# Jlink_V9.net
KiCad netlist of a schematic drawn in Altium Designer
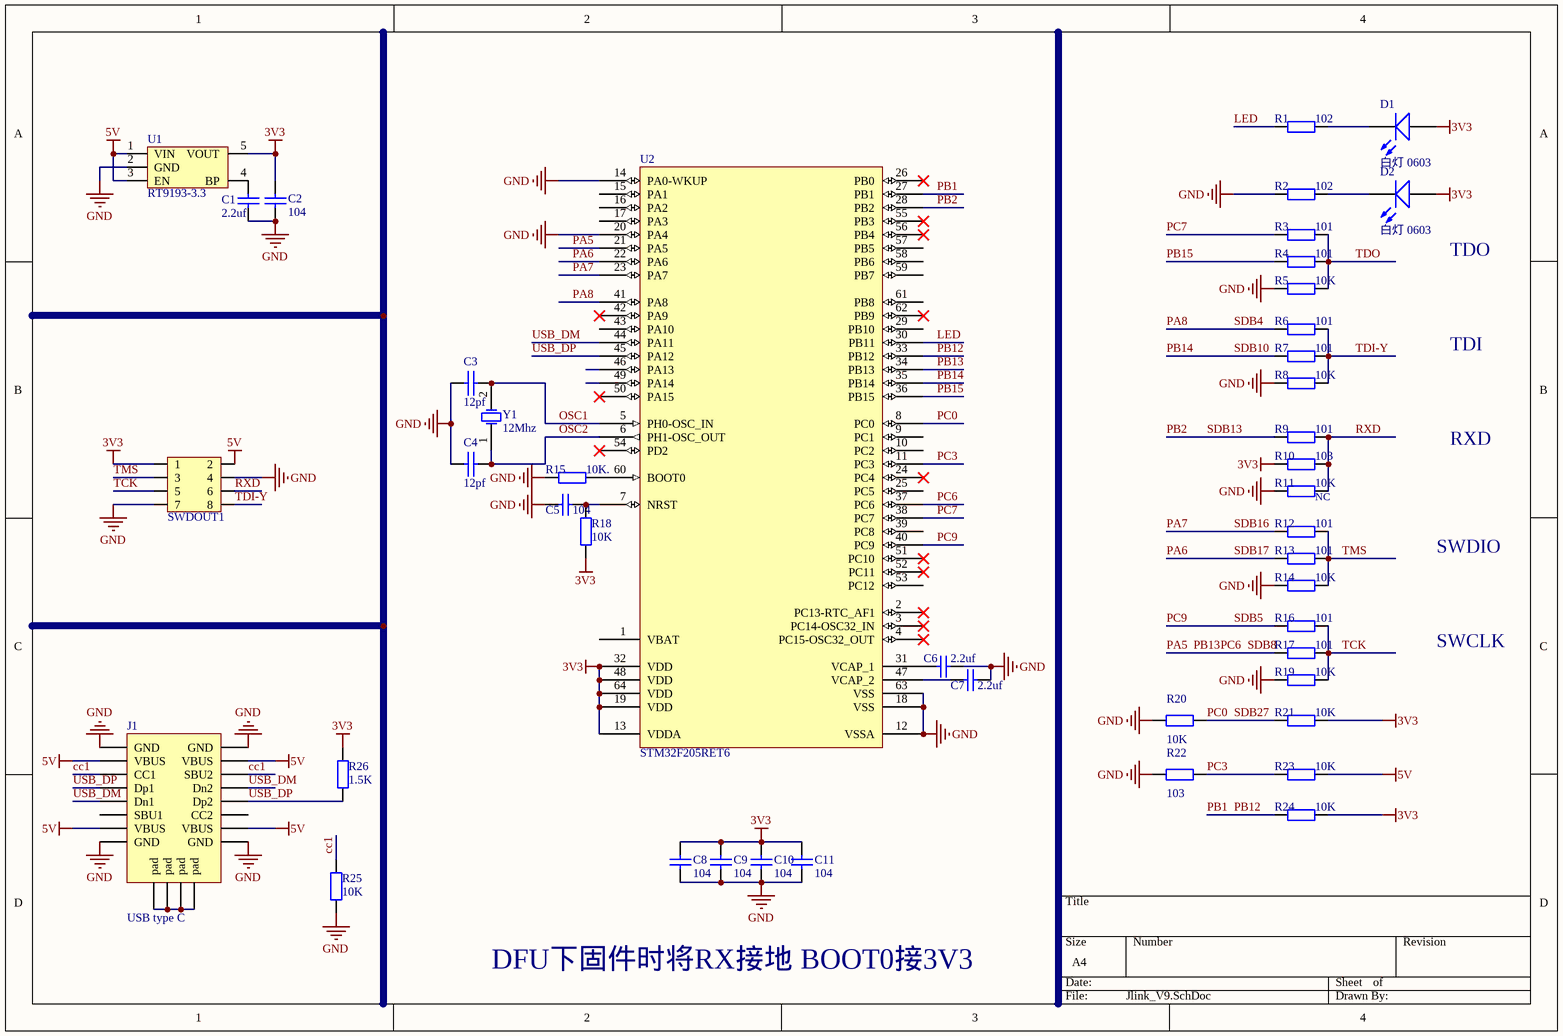
[diagram p0: Jlink_V9.SchDoc]

(export (version "E")
  (design (tool "Eeschema 10.0.6"))
  (components
    (comp (ref "C1")
      (value "2.2uf")
      (footprint "LC-0603_C")
      (description "Polarized Capacitor (Radial)")
      (fields (field (name "Comment") "Cap") (field (name "PUBLISHER") "Altium Limited"))
      (libsource (lib "Fantasy") (part "Cap"))
    )
    (comp (ref "C2")
      (value "104")
      (footprint "LC-0603_C")
      (description "Polarized Capacitor (Radial)")
      (fields (field (name "Comment") "Cap") (field (name "PUBLISHER") "Altium Limited"))
      (libsource (lib "Fantasy") (part "Cap"))
    )
    (comp (ref "C3") (value "12pf") (footprint "LC-0603_C") (libsource (lib "自创 (1)") (part "CAP")))
    (comp (ref "C4") (value "12pf") (footprint "LC-0603_C") (libsource (lib "自创 (1)") (part "CAP")))
    (comp (ref "C5")
      (value "104")
      (footprint "LC-0603_C")
      (description "Polarized Capacitor (Radial)")
      (fields (field (name "Comment") "Cap") (field (name "PUBLISHER") "Altium Limited"))
      (libsource (lib "Fantasy") (part "Cap"))
    )
    (comp (ref "C6")
      (value "2.2uf")
      (footprint "LC-0603_C")
      (description "Polarized Capacitor (Radial)")
      (fields (field (name "Comment") "Cap") (field (name "PUBLISHER") "Altium Limited"))
      (libsource (lib "Fantasy") (part "Cap"))
    )
    (comp (ref "C7")
      (value "2.2uf")
      (footprint "LC-0603_C")
      (description "Polarized Capacitor (Radial)")
      (fields (field (name "Comment") "Cap") (field (name "PUBLISHER") "Altium Limited"))
      (libsource (lib "Fantasy") (part "Cap"))
    )
    (comp (ref "C8")
      (value "104")
      (footprint "LC-0603_C")
      (description "Polarized Capacitor (Radial)")
      (fields (field (name "Comment") "Cap") (field (name "PUBLISHER") "Altium Limited"))
      (libsource (lib "Fantasy") (part "Cap"))
    )
    (comp (ref "C9")
      (value "104")
      (footprint "LC-0603_C")
      (description "Polarized Capacitor (Radial)")
      (fields (field (name "Comment") "Cap") (field (name "PUBLISHER") "Altium Limited"))
      (libsource (lib "Fantasy") (part "Cap"))
    )
    (comp (ref "C10")
      (value "104")
      (footprint "LC-0603_C")
      (description "Polarized Capacitor (Radial)")
      (fields (field (name "Comment") "Cap") (field (name "PUBLISHER") "Altium Limited"))
      (libsource (lib "Fantasy") (part "Cap"))
    )
    (comp (ref "C11")
      (value "104")
      (footprint "LC-0603_C")
      (description "Polarized Capacitor (Radial)")
      (fields (field (name "Comment") "Cap") (field (name "PUBLISHER") "Altium Limited"))
      (libsource (lib "Fantasy") (part "Cap"))
    )
    (comp (ref "D1")
      (value "白灯 0603")
      (footprint "0603_LED_S1")
      (description "发光二极管")
      (libsource (lib "Miscellaneous Devices LC") (part "0603 白灯"))
    )
    (comp (ref "D2")
      (value "白灯 0603")
      (footprint "0603_LED_S1")
      (description "发光二极管")
      (libsource (lib "Miscellaneous Devices LC") (part "0603 白灯"))
    )
    (comp (ref "J1")
      (value "USB type C")
      (footprint "USB Type-C-16Pin_A")
      (libsource (lib "XKZ") (part "USB_C"))
    )
    (comp (ref "R1")
      (value "102")
      (footprint "LC-0603_R")
      (description "Resistor Chip")
      (fields (field (name "PUBLISHER") "Altium Limited"))
      (libsource (lib "Fantasy") (part "Resistor"))
    )
    (comp (ref "R2")
      (value "102")
      (footprint "LC-0603_R")
      (description "Resistor Chip")
      (fields (field (name "PUBLISHER") "Altium Limited"))
      (libsource (lib "Fantasy") (part "Resistor"))
    )
    (comp (ref "R3")
      (value "101")
      (footprint "LC-0603_R")
      (description "Resistor Chip")
      (fields (field (name "PUBLISHER") "Altium Limited"))
      (libsource (lib "Fantasy") (part "Resistor"))
    )
    (comp (ref "R4")
      (value "101")
      (footprint "LC-0603_R")
      (description "Resistor Chip")
      (fields (field (name "PUBLISHER") "Altium Limited"))
      (libsource (lib "Fantasy") (part "Resistor"))
    )
    (comp (ref "R5")
      (value "10K")
      (footprint "LC-0603_R")
      (description "Resistor Chip")
      (fields (field (name "PUBLISHER") "Altium Limited"))
      (libsource (lib "Fantasy") (part "Resistor"))
    )
    (comp (ref "R6")
      (value "101")
      (footprint "LC-0603_R")
      (description "Resistor Chip")
      (fields (field (name "PUBLISHER") "Altium Limited"))
      (libsource (lib "Fantasy") (part "Resistor"))
    )
    (comp (ref "R7")
      (value "101")
      (footprint "LC-0603_R")
      (description "Resistor Chip")
      (fields (field (name "PUBLISHER") "Altium Limited"))
      (libsource (lib "Fantasy") (part "Resistor"))
    )
    (comp (ref "R8")
      (value "10K")
      (footprint "LC-0603_R")
      (description "Resistor Chip")
      (fields (field (name "PUBLISHER") "Altium Limited"))
      (libsource (lib "Fantasy") (part "Resistor"))
    )
    (comp (ref "R9")
      (value "101")
      (footprint "LC-0603_R")
      (description "Resistor Chip")
      (fields (field (name "PUBLISHER") "Altium Limited"))
      (libsource (lib "Fantasy") (part "Resistor"))
    )
    (comp (ref "R10")
      (value "103")
      (footprint "LC-0603_R")
      (description "Resistor Chip")
      (fields (field (name "PUBLISHER") "Altium Limited"))
      (libsource (lib "Fantasy") (part "Resistor"))
    )
    (comp (ref "R11")
      (value "10K")
      (footprint "LC-0603_R")
      (description "Resistor Chip")
      (fields (field (name "PUBLISHER") "Altium Limited"))
      (libsource (lib "Fantasy") (part "Resistor"))
    )
    (comp (ref "R12")
      (value "101")
      (footprint "LC-0603_R")
      (description "Resistor Chip")
      (fields (field (name "PUBLISHER") "Altium Limited"))
      (libsource (lib "Fantasy") (part "Resistor"))
    )
    (comp (ref "R13")
      (value "101")
      (footprint "LC-0603_R")
      (description "Resistor Chip")
      (fields (field (name "PUBLISHER") "Altium Limited"))
      (libsource (lib "Fantasy") (part "Resistor"))
    )
    (comp (ref "R14")
      (value "10K")
      (footprint "LC-0603_R")
      (description "Resistor Chip")
      (fields (field (name "PUBLISHER") "Altium Limited"))
      (libsource (lib "Fantasy") (part "Resistor"))
    )
    (comp (ref "R15")
      (value "10K.")
      (footprint "LC-0603_R")
      (description "Resistor Chip")
      (fields (field (name "PUBLISHER") "Altium Limited"))
      (libsource (lib "Fantasy") (part "Resistor"))
    )
    (comp (ref "R16")
      (value "101")
      (footprint "LC-0603_R")
      (description "Resistor Chip")
      (fields (field (name "PUBLISHER") "Altium Limited"))
      (libsource (lib "Fantasy") (part "Resistor"))
    )
    (comp (ref "R17")
      (value "101")
      (footprint "LC-0603_R")
      (description "Resistor Chip")
      (fields (field (name "PUBLISHER") "Altium Limited"))
      (libsource (lib "Fantasy") (part "Resistor"))
    )
    (comp (ref "R18")
      (value "10K")
      (footprint "LC-0603_R")
      (description "Resistor Chip")
      (fields (field (name "PUBLISHER") "Altium Limited"))
      (libsource (lib "") (part "Resistor_1"))
    )
    (comp (ref "R19")
      (value "10K")
      (footprint "LC-0603_R")
      (description "Resistor Chip")
      (fields (field (name "PUBLISHER") "Altium Limited"))
      (libsource (lib "Fantasy") (part "Resistor"))
    )
    (comp (ref "R20")
      (value "10K")
      (footprint "LC-0603_R")
      (description "Resistor Chip")
      (fields (field (name "PUBLISHER") "Altium Limited"))
      (libsource (lib "Fantasy") (part "Resistor"))
    )
    (comp (ref "R21")
      (value "10K")
      (footprint "LC-0603_R")
      (description "Resistor Chip")
      (fields (field (name "PUBLISHER") "Altium Limited"))
      (libsource (lib "Fantasy") (part "Resistor"))
    )
    (comp (ref "R22")
      (value "103")
      (footprint "LC-0603_R")
      (description "Resistor Chip")
      (fields (field (name "PUBLISHER") "Altium Limited"))
      (libsource (lib "Fantasy") (part "Resistor"))
    )
    (comp (ref "R23")
      (value "10K")
      (footprint "LC-0603_R")
      (description "Resistor Chip")
      (fields (field (name "PUBLISHER") "Altium Limited"))
      (libsource (lib "Fantasy") (part "Resistor"))
    )
    (comp (ref "R24")
      (value "10K")
      (footprint "LC-0603_R")
      (description "Resistor Chip")
      (fields (field (name "PUBLISHER") "Altium Limited"))
      (libsource (lib "Fantasy") (part "Resistor"))
    )
    (comp (ref "R25")
      (value "10K")
      (footprint "LC-0603_R")
      (description "Resistor")
      (fields (field (name "Comment") "Res2") (field (name "PUBLISHER") "Altium Limited"))
      (libsource (lib "XKZ") (part "Res2"))
    )
    (comp (ref "R26")
      (value "1.5K")
      (footprint "LC-0603_R")
      (description "Resistor")
      (fields (field (name "Comment") "Res2") (field (name "PUBLISHER") "Altium Limited"))
      (libsource (lib "XKZ") (part "Res2"))
    )
    (comp (ref "SWDOUT1")
      (value "HDR2x6_2.54")
      (footprint "PCB_ConnectorHDR:HDR2X4_2.54_180H")
      (description "Header")
      (libsource (lib "SCH_ConnectorHDR") (part "HDR2x4_2.54"))
    )
    (comp (ref "U1")
      (value "RT9193-3.3")
      (footprint "SOT23-5N")
      (description "3.3V超低压差LDO")
      (libsource (lib "Fantasy") (part "RT9193-33"))
    )
    (comp (ref "U2")
      (value "STM32F205RET6")
      (footprint "LQFP64 10x10_N")
      (description "Microcontroller   ST")
      (libsource (lib "Fantasy") (part "STM32F205RET6"))
    )
    (comp (ref "Y1")
      (value "12Mhz")
      (footprint "XT_5032_2")
      (description "Crystal Oscillator")
      (fields (field (name "PUBLISHER") "Altium Limited"))
      (libsource (lib "自创 (1)") (part "XTAL_1"))
    )
  )
  (nets
    (net (code "1") (name "/LED") (class "Default")
      (node (ref "R1") (pin "1") (pinfunction "1_1") (pintype "passive"))
      (node (ref "U2") (pin "30") (pinfunction "PB11_30") (pintype "bidirectional"))
    )
    (net (code "2") (name "/OSC1") (class "Default")
      (node (ref "C3") (pin "2") (pinfunction "2_2") (pintype "passive"))
      (node (ref "U2") (pin "5") (pinfunction "PH0-OSC_IN_5") (pintype "input"))
      (node (ref "Y1") (pin "2") (pinfunction "OSC2_2") (pintype "passive"))
    )
    (net (code "3") (name "/OSC2") (class "Default")
      (node (ref "C4") (pin "1") (pinfunction "1_1") (pintype "passive"))
      (node (ref "U2") (pin "6") (pinfunction "PH1-OSC_OUT_6") (pintype "output"))
      (node (ref "Y1") (pin "1") (pinfunction "OSC1_1") (pintype "passive"))
    )
    (net (code "4") (name "/PA5") (class "Default")
      (node (ref "R17") (pin "1") (pinfunction "1_1") (pintype "passive"))
      (node (ref "U2") (pin "21") (pinfunction "PA5_21") (pintype "bidirectional"))
      (node (ref "U2") (pin "34") (pinfunction "PB13_34") (pintype "bidirectional"))
      (node (ref "U2") (pin "37") (pinfunction "PC6_37") (pintype "bidirectional"))
    )
    (net (code "5") (name "/PA6") (class "Default")
      (node (ref "R13") (pin "1") (pinfunction "1_1") (pintype "passive"))
      (node (ref "U2") (pin "22") (pinfunction "PA6_22") (pintype "bidirectional"))
    )
    (net (code "6") (name "/PA7") (class "Default")
      (node (ref "R12") (pin "1") (pinfunction "1_1") (pintype "passive"))
      (node (ref "U2") (pin "23") (pinfunction "PA7_23") (pintype "bidirectional"))
    )
    (net (code "7") (name "/PA8") (class "Default")
      (node (ref "R6") (pin "1") (pinfunction "1_1") (pintype "passive"))
      (node (ref "U2") (pin "41") (pinfunction "PA8_41") (pintype "bidirectional"))
    )
    (net (code "8") (name "/PB1") (class "Default")
      (node (ref "R24") (pin "1") (pinfunction "1_1") (pintype "passive"))
      (node (ref "U2") (pin "27") (pinfunction "PB1_27") (pintype "bidirectional"))
      (node (ref "U2") (pin "33") (pinfunction "PB12_33") (pintype "bidirectional"))
    )
    (net (code "9") (name "/PB2") (class "Default")
      (node (ref "R9") (pin "1") (pinfunction "1_1") (pintype "passive"))
      (node (ref "U2") (pin "28") (pinfunction "PB2_28") (pintype "bidirectional"))
    )
    (net (code "10") (name "/PB14") (class "Default")
      (node (ref "R7") (pin "1") (pinfunction "1_1") (pintype "passive"))
      (node (ref "U2") (pin "35") (pinfunction "PB14_35") (pintype "bidirectional"))
    )
    (net (code "11") (name "/PB15") (class "Default")
      (node (ref "R4") (pin "1") (pinfunction "1_1") (pintype "passive"))
      (node (ref "U2") (pin "36") (pinfunction "PB15_36") (pintype "bidirectional"))
    )
    (net (code "12") (name "/PC0") (class "Default")
      (node (ref "R20") (pin "2") (pinfunction "2_2") (pintype "passive"))
      (node (ref "R21") (pin "1") (pinfunction "1_1") (pintype "passive"))
      (node (ref "U2") (pin "8") (pinfunction "PC0_8") (pintype "bidirectional"))
    )
    (net (code "13") (name "/PC3") (class "Default")
      (node (ref "R22") (pin "2") (pinfunction "2_2") (pintype "passive"))
      (node (ref "R23") (pin "1") (pinfunction "1_1") (pintype "passive"))
      (node (ref "U2") (pin "11") (pinfunction "PC3_11") (pintype "bidirectional"))
    )
    (net (code "14") (name "/PC7") (class "Default")
      (node (ref "R3") (pin "1") (pinfunction "1_1") (pintype "passive"))
      (node (ref "U2") (pin "38") (pinfunction "PC7_38") (pintype "bidirectional"))
    )
    (net (code "15") (name "/PC9") (class "Default")
      (node (ref "R16") (pin "1") (pinfunction "1_1") (pintype "passive"))
      (node (ref "U2") (pin "40") (pinfunction "PC9_40") (pintype "bidirectional"))
    )
    (net (code "16") (name "/RXD") (class "Default")
      (node (ref "R10") (pin "2") (pinfunction "2_2") (pintype "passive"))
      (node (ref "R11") (pin "2") (pinfunction "2_2") (pintype "passive"))
      (node (ref "R9") (pin "2") (pinfunction "2_2") (pintype "passive"))
      (node (ref "SWDOUT1") (pin "6") (pinfunction "6_6") (pintype "passive"))
    )
    (net (code "17") (name "/TCK") (class "Default")
      (node (ref "R16") (pin "2") (pinfunction "2_2") (pintype "passive"))
      (node (ref "R17") (pin "2") (pinfunction "2_2") (pintype "passive"))
      (node (ref "R19") (pin "2") (pinfunction "2_2") (pintype "passive"))
      (node (ref "SWDOUT1") (pin "5") (pinfunction "5_5") (pintype "passive"))
    )
    (net (code "18") (name "/TDI-Y") (class "Default")
      (node (ref "R6") (pin "2") (pinfunction "2_2") (pintype "passive"))
      (node (ref "R7") (pin "2") (pinfunction "2_2") (pintype "passive"))
      (node (ref "R8") (pin "2") (pinfunction "2_2") (pintype "passive"))
      (node (ref "SWDOUT1") (pin "8") (pinfunction "8_8") (pintype "passive"))
    )
    (net (code "19") (name "/TDO") (class "Default")
      (node (ref "R3") (pin "2") (pinfunction "2_2") (pintype "passive"))
      (node (ref "R4") (pin "2") (pinfunction "2_2") (pintype "passive"))
      (node (ref "R5") (pin "2") (pinfunction "2_2") (pintype "passive"))
    )
    (net (code "20") (name "/TMS") (class "Default")
      (node (ref "R12") (pin "2") (pinfunction "2_2") (pintype "passive"))
      (node (ref "R13") (pin "2") (pinfunction "2_2") (pintype "passive"))
      (node (ref "R14") (pin "2") (pinfunction "2_2") (pintype "passive"))
      (node (ref "SWDOUT1") (pin "3") (pinfunction "3_3") (pintype "passive"))
    )
    (net (code "21") (name "/USB_DM") (class "Default")
      (node (ref "J1") (pin "A7") (pinfunction "Dn1_A7") (pintype "passive"))
      (node (ref "J1") (pin "B7") (pinfunction "Dn2_B7") (pintype "passive"))
      (node (ref "U2") (pin "44") (pinfunction "PA11_44") (pintype "bidirectional"))
    )
    (net (code "22") (name "/USB_DP") (class "Default")
      (node (ref "J1") (pin "A6") (pinfunction "Dp1_A6") (pintype "passive"))
      (node (ref "J1") (pin "B6") (pinfunction "Dp2_B6") (pintype "passive"))
      (node (ref "R26") (pin "2") (pinfunction "2_2") (pintype "passive"))
      (node (ref "U2") (pin "45") (pinfunction "PA12_45") (pintype "bidirectional"))
    )
    (net (code "23") (name "/cc1") (class "Default")
      (node (ref "J1") (pin "A5") (pinfunction "CC1_A5") (pintype "passive"))
      (node (ref "J1") (pin "B8") (pinfunction "SBU2_B8") (pintype "passive"))
      (node (ref "R25") (pin "1") (pinfunction "1_1") (pintype "passive"))
    )
    (net (code "24") (name "3V3") (class "Default")
      (node (ref "C10") (pin "2") (pinfunction "2_2") (pintype "passive"))
      (node (ref "C11") (pin "2") (pinfunction "2_2") (pintype "passive"))
      (node (ref "C2") (pin "2") (pinfunction "2_2") (pintype "passive"))
      (node (ref "C8") (pin "2") (pinfunction "2_2") (pintype "passive"))
      (node (ref "C9") (pin "2") (pinfunction "2_2") (pintype "passive"))
      (node (ref "D1") (pin "A") (pinfunction "A_A") (pintype "passive"))
      (node (ref "D2") (pin "A") (pinfunction "A_A") (pintype "passive"))
      (node (ref "R10") (pin "1") (pinfunction "1_1") (pintype "passive"))
      (node (ref "R18") (pin "1") (pinfunction "1_1") (pintype "passive"))
      (node (ref "R21") (pin "2") (pinfunction "2_2") (pintype "passive"))
      (node (ref "R24") (pin "2") (pinfunction "2_2") (pintype "passive"))
      (node (ref "R26") (pin "1") (pinfunction "1_1") (pintype "passive"))
      (node (ref "SWDOUT1") (pin "1") (pinfunction "1_1") (pintype "passive"))
      (node (ref "U1") (pin "5") (pinfunction "VOUT_5") (pintype "passive"))
      (node (ref "U2") (pin "13") (pinfunction "VDDA_13") (pintype "power_in"))
      (node (ref "U2") (pin "19") (pinfunction "VDD_19") (pintype "power_in"))
      (node (ref "U2") (pin "32") (pinfunction "VDD_32") (pintype "power_in"))
      (node (ref "U2") (pin "48") (pinfunction "VDD_48") (pintype "power_in"))
      (node (ref "U2") (pin "64") (pinfunction "VDD_64") (pintype "power_in"))
    )
    (net (code "25") (name "5V") (class "Default")
      (node (ref "J1") (pin "A4") (pinfunction "VBUS_A4") (pintype "passive"))
      (node (ref "J1") (pin "A9") (pinfunction "VBUS_A9") (pintype "passive"))
      (node (ref "J1") (pin "B4") (pinfunction "VBUS_B4") (pintype "passive"))
      (node (ref "J1") (pin "B9") (pinfunction "VBUS_B9") (pintype "passive"))
      (node (ref "R23") (pin "2") (pinfunction "2_2") (pintype "passive"))
      (node (ref "SWDOUT1") (pin "2") (pinfunction "2_2") (pintype "passive"))
      (node (ref "U1") (pin "1") (pinfunction "VIN_1") (pintype "passive"))
      (node (ref "U1") (pin "3") (pinfunction "EN_3") (pintype "passive"))
    )
    (net (code "26") (name "GND") (class "Default")
      (node (ref "C1") (pin "1") (pinfunction "1_1") (pintype "passive"))
      (node (ref "C10") (pin "1") (pinfunction "1_1") (pintype "passive"))
      (node (ref "C11") (pin "1") (pinfunction "1_1") (pintype "passive"))
      (node (ref "C2") (pin "1") (pinfunction "1_1") (pintype "passive"))
      (node (ref "C3") (pin "1") (pinfunction "1_1") (pintype "passive"))
      (node (ref "C4") (pin "2") (pinfunction "2_2") (pintype "passive"))
      (node (ref "C5") (pin "2") (pinfunction "2_2") (pintype "passive"))
      (node (ref "C6") (pin "1") (pinfunction "1_1") (pintype "passive"))
      (node (ref "C7") (pin "1") (pinfunction "1_1") (pintype "passive"))
      (node (ref "C8") (pin "1") (pinfunction "1_1") (pintype "passive"))
      (node (ref "C9") (pin "1") (pinfunction "1_1") (pintype "passive"))
      (node (ref "J1") (pin "A1") (pinfunction "GND_A1") (pintype "passive"))
      (node (ref "J1") (pin "A12") (pinfunction "GND_A12") (pintype "passive"))
      (node (ref "J1") (pin "B1") (pinfunction "GND_B1") (pintype "passive"))
      (node (ref "J1") (pin "B12") (pinfunction "GND_B12") (pintype "passive"))
      (node (ref "R11") (pin "1") (pinfunction "1_1") (pintype "passive"))
      (node (ref "R14") (pin "1") (pinfunction "1_1") (pintype "passive"))
      (node (ref "R15") (pin "1") (pinfunction "1_1") (pintype "passive"))
      (node (ref "R19") (pin "1") (pinfunction "1_1") (pintype "passive"))
      (node (ref "R2") (pin "1") (pinfunction "1_1") (pintype "passive"))
      (node (ref "R20") (pin "1") (pinfunction "1_1") (pintype "passive"))
      (node (ref "R22") (pin "1") (pinfunction "1_1") (pintype "passive"))
      (node (ref "R25") (pin "2") (pinfunction "2_2") (pintype "passive"))
      (node (ref "R5") (pin "1") (pinfunction "1_1") (pintype "passive"))
      (node (ref "R8") (pin "1") (pinfunction "1_1") (pintype "passive"))
      (node (ref "SWDOUT1") (pin "4") (pinfunction "4_4") (pintype "passive"))
      (node (ref "SWDOUT1") (pin "7") (pinfunction "7_7") (pintype "passive"))
      (node (ref "U1") (pin "2") (pinfunction "GND_2") (pintype "passive"))
      (node (ref "U2") (pin "12") (pinfunction "VSSA_12") (pintype "power_in"))
      (node (ref "U2") (pin "14") (pinfunction "PA0-WKUP_14") (pintype "bidirectional"))
      (node (ref "U2") (pin "18") (pinfunction "VSS_18") (pintype "power_in"))
      (node (ref "U2") (pin "20") (pinfunction "PA4_20") (pintype "bidirectional"))
      (node (ref "U2") (pin "63") (pinfunction "VSS_63") (pintype "power_in"))
    )
    (net (code "27") (name "Net-(D1-PadK)") (class "Default")
      (node (ref "D1") (pin "K") (pinfunction "K_K") (pintype "passive"))
      (node (ref "R1") (pin "2") (pinfunction "2_2") (pintype "passive"))
    )
    (net (code "28") (name "Net-(D2-PadK)") (class "Default")
      (node (ref "D2") (pin "K") (pinfunction "K_K") (pintype "passive"))
      (node (ref "R2") (pin "2") (pinfunction "2_2") (pintype "passive"))
    )
    (net (code "29") (name "Net-(J1-pad)") (class "Default")
      (node (ref "J1") (pin "0") (pinfunction "pad_0") (pintype "passive"))
    )
    (net (code "30") (name "Net-(U1-BP)") (class "Default")
      (node (ref "C1") (pin "2") (pinfunction "2_2") (pintype "passive"))
      (node (ref "U1") (pin "4") (pinfunction "BP_4") (pintype "passive"))
    )
    (net (code "31") (name "Net-(U2-BOOT0)") (class "Default")
      (node (ref "R15") (pin "2") (pinfunction "2_2") (pintype "passive"))
      (node (ref "U2") (pin "60") (pinfunction "BOOT0_60") (pintype "input"))
    )
    (net (code "32") (name "Net-(U2-NRST)") (class "Default")
      (node (ref "C5") (pin "1") (pinfunction "1_1") (pintype "passive"))
      (node (ref "R18") (pin "2") (pinfunction "2_2") (pintype "passive"))
      (node (ref "U2") (pin "7") (pinfunction "NRST_7") (pintype "bidirectional"))
    )
    (net (code "33") (name "Net-(U2-VCAP_1)") (class "Default")
      (node (ref "C6") (pin "2") (pinfunction "2_2") (pintype "passive"))
      (node (ref "U2") (pin "31") (pinfunction "VCAP_1_31") (pintype "power_in"))
    )
    (net (code "34") (name "Net-(U2-VCAP_2)") (class "Default")
      (node (ref "C7") (pin "2") (pinfunction "2_2") (pintype "passive"))
      (node (ref "U2") (pin "47") (pinfunction "VCAP_2_47") (pintype "power_in"))
    )
    (net (code "35") (name "unconnected-(J1-CC2-PadB5)") (class "Default")
      (node (ref "J1") (pin "B5") (pinfunction "CC2_B5") (pintype "passive"))
    )
    (net (code "36") (name "unconnected-(J1-SBU1-PadA8)") (class "Default")
      (node (ref "J1") (pin "A8") (pinfunction "SBU1_A8") (pintype "passive"))
    )
    (net (code "37") (name "unconnected-(U2-PA1-Pad15)") (class "Default")
      (node (ref "U2") (pin "15") (pinfunction "PA1_15") (pintype "bidirectional"))
    )
    (net (code "38") (name "unconnected-(U2-PA2-Pad16)") (class "Default")
      (node (ref "U2") (pin "16") (pinfunction "PA2_16") (pintype "bidirectional"))
    )
    (net (code "39") (name "unconnected-(U2-PA3-Pad17)") (class "Default")
      (node (ref "U2") (pin "17") (pinfunction "PA3_17") (pintype "bidirectional"))
    )
    (net (code "40") (name "unconnected-(U2-PA9-Pad42)") (class "Default")
      (node (ref "U2") (pin "42") (pinfunction "PA9_42") (pintype "bidirectional+no_connect"))
    )
    (net (code "41") (name "unconnected-(U2-PA10-Pad43)") (class "Default")
      (node (ref "U2") (pin "43") (pinfunction "PA10_43") (pintype "bidirectional"))
    )
    (net (code "42") (name "unconnected-(U2-PA13-Pad46)") (class "Default")
      (node (ref "U2") (pin "46") (pinfunction "PA13_46") (pintype "bidirectional"))
    )
    (net (code "43") (name "unconnected-(U2-PA14-Pad49)") (class "Default")
      (node (ref "U2") (pin "49") (pinfunction "PA14_49") (pintype "bidirectional"))
    )
    (net (code "44") (name "unconnected-(U2-PA15-Pad50)") (class "Default")
      (node (ref "U2") (pin "50") (pinfunction "PA15_50") (pintype "bidirectional+no_connect"))
    )
    (net (code "45") (name "unconnected-(U2-PB0-Pad26)") (class "Default")
      (node (ref "U2") (pin "26") (pinfunction "PB0_26") (pintype "bidirectional+no_connect"))
    )
    (net (code "46") (name "unconnected-(U2-PB3-Pad55)") (class "Default")
      (node (ref "U2") (pin "55") (pinfunction "PB3_55") (pintype "bidirectional+no_connect"))
    )
    (net (code "47") (name "unconnected-(U2-PB4-Pad56)") (class "Default")
      (node (ref "U2") (pin "56") (pinfunction "PB4_56") (pintype "bidirectional+no_connect"))
    )
    (net (code "48") (name "unconnected-(U2-PB5-Pad57)") (class "Default")
      (node (ref "U2") (pin "57") (pinfunction "PB5_57") (pintype "bidirectional"))
    )
    (net (code "49") (name "unconnected-(U2-PB6-Pad58)") (class "Default")
      (node (ref "U2") (pin "58") (pinfunction "PB6_58") (pintype "bidirectional"))
    )
    (net (code "50") (name "unconnected-(U2-PB7-Pad59)") (class "Default")
      (node (ref "U2") (pin "59") (pinfunction "PB7_59") (pintype "bidirectional"))
    )
    (net (code "51") (name "unconnected-(U2-PB8-Pad61)") (class "Default")
      (node (ref "U2") (pin "61") (pinfunction "PB8_61") (pintype "bidirectional"))
    )
    (net (code "52") (name "unconnected-(U2-PB9-Pad62)") (class "Default")
      (node (ref "U2") (pin "62") (pinfunction "PB9_62") (pintype "bidirectional+no_connect"))
    )
    (net (code "53") (name "unconnected-(U2-PB10-Pad29)") (class "Default")
      (node (ref "U2") (pin "29") (pinfunction "PB10_29") (pintype "bidirectional"))
    )
    (net (code "54") (name "unconnected-(U2-PC1-Pad9)") (class "Default")
      (node (ref "U2") (pin "9") (pinfunction "PC1_9") (pintype "bidirectional"))
    )
    (net (code "55") (name "unconnected-(U2-PC2-Pad10)") (class "Default")
      (node (ref "U2") (pin "10") (pinfunction "PC2_10") (pintype "bidirectional"))
    )
    (net (code "56") (name "unconnected-(U2-PC4-Pad24)") (class "Default")
      (node (ref "U2") (pin "24") (pinfunction "PC4_24") (pintype "bidirectional+no_connect"))
    )
    (net (code "57") (name "unconnected-(U2-PC5-Pad25)") (class "Default")
      (node (ref "U2") (pin "25") (pinfunction "PC5_25") (pintype "bidirectional"))
    )
    (net (code "58") (name "unconnected-(U2-PC8-Pad39)") (class "Default")
      (node (ref "U2") (pin "39") (pinfunction "PC8_39") (pintype "bidirectional"))
    )
    (net (code "59") (name "unconnected-(U2-PC10-Pad51)") (class "Default")
      (node (ref "U2") (pin "51") (pinfunction "PC10_51") (pintype "bidirectional+no_connect"))
    )
    (net (code "60") (name "unconnected-(U2-PC11-Pad52)") (class "Default")
      (node (ref "U2") (pin "52") (pinfunction "PC11_52") (pintype "bidirectional+no_connect"))
    )
    (net (code "61") (name "unconnected-(U2-PC12-Pad53)") (class "Default")
      (node (ref "U2") (pin "53") (pinfunction "PC12_53") (pintype "bidirectional"))
    )
    (net (code "62") (name "unconnected-(U2-PC13-RTC_AF1-Pad2)") (class "Default")
      (node (ref "U2") (pin "2") (pinfunction "PC13-RTC_AF1_2") (pintype "bidirectional+no_connect"))
    )
    (net (code "63") (name "unconnected-(U2-PC14-OSC32_IN-Pad3)") (class "Default")
      (node (ref "U2") (pin "3") (pinfunction "PC14-OSC32_IN_3") (pintype "bidirectional+no_connect"))
    )
    (net (code "64") (name "unconnected-(U2-PC15-OSC32_OUT-Pad4)") (class "Default")
      (node (ref "U2") (pin "4") (pinfunction "PC15-OSC32_OUT_4") (pintype "bidirectional+no_connect"))
    )
    (net (code "65") (name "unconnected-(U2-PD2-Pad54)") (class "Default")
      (node (ref "U2") (pin "54") (pinfunction "PD2_54") (pintype "bidirectional+no_connect"))
    )
    (net (code "66") (name "unconnected-(U2-VBAT-Pad1)") (class "Default")
      (node (ref "U2") (pin "1") (pinfunction "VBAT_1") (pintype "power_in"))
    )
  )
)
